# schematic4.net
KiCad netlist of a schematic drawn in Altium Designer
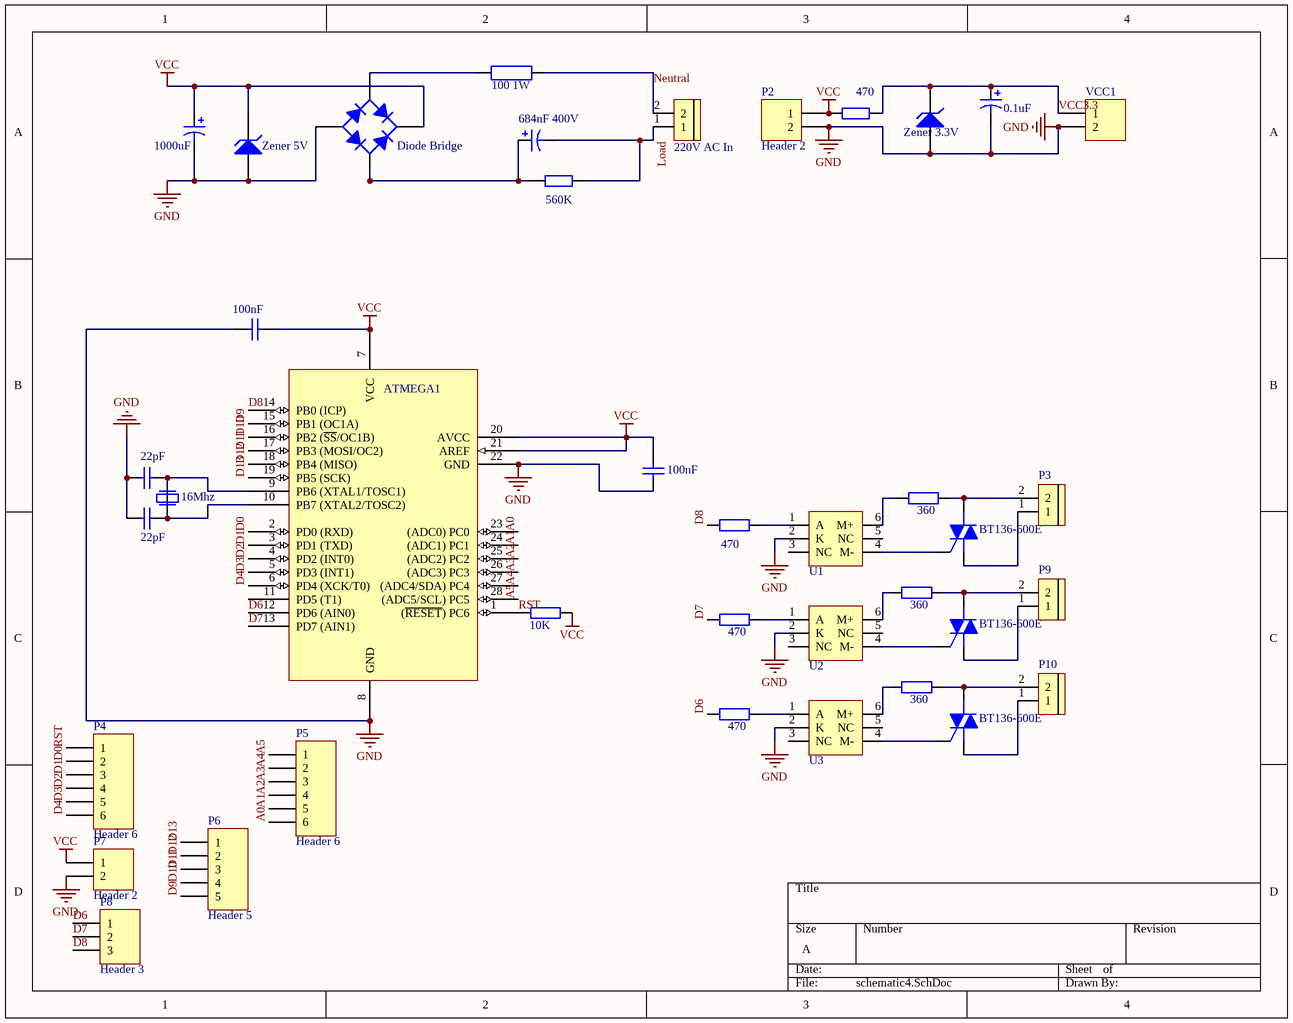
[diagram p0: schematic4.SchDoc]

(export (version "E")
  (design (tool "Eeschema 10.0.6"))
  (components
    (comp (ref "ATMEGA1")
      (value "ATMEGA8_DIP28")
      (footprint "DIP-28")
      (description "Atmel Microcontroller - Library created by carel..  <www.mpfreezone.com>")
      (libsource (lib "AVR") (part "ATMEGA8_DIP28"))
    )
    (comp (ref "C1")
      (value "0.1uF")
      (footprint "C3MM")
      (description "Polarized Capacitor (Axial)")
      (fields (field (name "PUBLISHER") "Altium Limited"))
      (libsource (lib "NBBLib 14-03-2012") (part "Cap Pol 3mm"))
    )
    (comp (ref "C2")
      (value "684nF 400V")
      (footprint "C10mm")
      (description "Polarized Capacitor (Axial)")
      (fields (field (name "PUBLISHER") "Altium Limited"))
      (libsource (lib "NBBLib 14-03-2012") (part "Cap Pol 12mm"))
    )
    (comp (ref "C3")
      (value "1000uF")
      (footprint "C10mm")
      (description "Polarized Capacitor (Axial)")
      (fields (field (name "PUBLISHER") "Altium Limited"))
      (libsource (lib "NBBLib 14-03-2012") (part "Cap Pol 8mm"))
    )
    (comp (ref "C4")
      (value "100nF")
      (footprint "Tu-pico")
      (description "Capacitor")
      (fields (field (name "PUBLISHER") "Altium Limited"))
      (libsource (lib "NBBLib 14-03-2012") (part "CapCeramic"))
    )
    (comp (ref "C5")
      (value "22pF")
      (footprint "Tu-pico")
      (description "Capacitor")
      (fields (field (name "PUBLISHER") "Altium Limited"))
      (libsource (lib "NBBLib 14-03-2012") (part "CapCeramic"))
    )
    (comp (ref "C6")
      (value "100nF")
      (footprint "Tu-pico")
      (description "Capacitor")
      (fields (field (name "PUBLISHER") "Altium Limited"))
      (libsource (lib "NBBLib 14-03-2012") (part "CapCeramic"))
    )
    (comp (ref "C7")
      (value "22pF")
      (footprint "Tu-pico")
      (description "Capacitor")
      (fields (field (name "PUBLISHER") "Altium Limited"))
      (libsource (lib "NBBLib 14-03-2012") (part "CapCeramic"))
    )
    (comp (ref "Crystal1") (value "16Mhz") (footprint "XTAL") (libsource (lib "tung k6") (part "XTAL")))
    (comp (ref "D1")
      (value "Diode Bridge")
      (footprint "D-38")
      (description "Full Wave Diode Bridge")
      (fields (field (name "PUBLISHER") "Altium Limited"))
      (libsource (lib "Miscellaneous Devices") (part "Bridge1"))
    )
    (comp (ref "D2")
      (value "Zener 3.3V")
      (footprint "DIODE/NOM/0.5A")
      (description "Zener Diode")
      (fields (field (name "PUBLISHER") "Altium Limited"))
      (libsource (lib "NBBLib 14-03-2012") (part "Diode Zener"))
    )
    (comp (ref "D3")
      (value "Zener 5V")
      (footprint "DIODE/NOM/0.5A")
      (description "Zener Diode")
      (fields (field (name "VOLTAGE") "5") (field (name "PUBLISHER") "Altium Limited"))
      (libsource (lib "NBBLib 14-03-2012") (part "Diode Zener"))
    )
    (comp (ref "P1")
      (value "220V AC In")
      (footprint "BIG_Header 2")
      (libsource (lib "NBBLib 14-03-2012") (part "BIG_Header 2"))
    )
    (comp (ref "P2")
      (value "Header 2")
      (footprint "HDR1X2")
      (description "Header, 2-Pin")
      (fields (field (name "PUBLISHER") "Altium Limited"))
      (libsource (lib "") (part "Header 2_1"))
    )
    (comp (ref "P3")
      (value "BIG_Header 2")
      (footprint "BIG_Header 2")
      (libsource (lib "NBBLib 14-03-2012") (part "BIG_Header 2"))
    )
    (comp (ref "P4")
      (value "Header 6")
      (footprint "HDR1X6")
      (description "Header, 6-Pin")
      (fields (field (name "PUBLISHER") "Altium Limited"))
      (libsource (lib "Miscellaneous Connectors") (part "Header 6"))
    )
    (comp (ref "P5")
      (value "Header 6")
      (footprint "HDR1X6")
      (description "Header, 6-Pin")
      (fields (field (name "PUBLISHER") "Altium Limited"))
      (libsource (lib "Miscellaneous Connectors") (part "Header 6"))
    )
    (comp (ref "P6")
      (value "Header 5")
      (footprint "HDR1X5")
      (description "Header, 5-Pin")
      (fields (field (name "PUBLISHER") "Altium Limited"))
      (libsource (lib "NBBLib 14-03-2012") (part "Header 5"))
    )
    (comp (ref "P7")
      (value "Header 2")
      (footprint "HDR1X2")
      (description "Header, 2-Pin")
      (fields (field (name "PUBLISHER") "Altium Limited"))
      (libsource (lib "Miscellaneous Connectors") (part "Header 2"))
    )
    (comp (ref "P8")
      (value "Header 3")
      (footprint "HDR1X3")
      (description "Header, 3-Pin")
      (fields (field (name "PUBLISHER") "Altium Limited"))
      (libsource (lib "NBBLib 14-03-2012") (part "Header 3"))
    )
    (comp (ref "P9")
      (value "BIG_Header 2")
      (footprint "BIG_Header 2")
      (libsource (lib "NBBLib 14-03-2012") (part "BIG_Header 2"))
    )
    (comp (ref "P10")
      (value "BIG_Header 2")
      (footprint "BIG_Header 2")
      (libsource (lib "NBBLib 14-03-2012") (part "BIG_Header 2"))
    )
    (comp (ref "Q1")
      (value "BT136-600E")
      (footprint "BTA6-600")
      (description "Silicon Bidirectional Triode Thyristor")
      (fields (field (name "PUBLISHER") "Altium Limited"))
      (libsource (lib "NBBLib 14-03-2012") (part "BTA12-600"))
    )
    (comp (ref "Q2")
      (value "BT136-600E")
      (footprint "BTA6-600")
      (description "Silicon Bidirectional Triode Thyristor")
      (fields (field (name "PUBLISHER") "Altium Limited"))
      (libsource (lib "NBBLib 14-03-2012") (part "BTA12-600"))
    )
    (comp (ref "Q3")
      (value "BT136-600E")
      (footprint "BTA6-600")
      (description "Silicon Bidirectional Triode Thyristor")
      (fields (field (name "PUBLISHER") "Altium Limited"))
      (libsource (lib "NBBLib 14-03-2012") (part "BTA12-600"))
    )
    (comp (ref "R1")
      (value "100 1W")
      (footprint "DIEN TRO 1W (tube)")
      (description "1W Res Power")
      (fields (field (name "VOLTAGE") "400") (field (name "CREATOR") "Nguyen Ba Bien"))
      (libsource (lib "NBBLib 14-03-2012") (part "Res 1W"))
    )
    (comp (ref "R2")
      (value "470")
      (footprint "DIEN TRO 1/4 W")
      (description "Resistor")
      (fields (field (name "Comment") "R0.4W") (field (name "PUBLISHER") "Altium Limited"))
      (libsource (lib "NBBLib 14-03-2012") (part "Res 1/4 W"))
    )
    (comp (ref "R3")
      (value "560K")
      (footprint "AXIAL-0.4")
      (description "Resistor")
      (fields (field (name "PUBLISHER") "Altium Limited"))
      (libsource (lib "Miscellaneous Devices") (part "Res2"))
    )
    (comp (ref "R4")
      (value "470")
      (footprint "R1/4W")
      (description "Resistor")
      (libsource (lib "t.thien") (part "R1/4W"))
    )
    (comp (ref "R5")
      (value "360")
      (footprint "R1/4W")
      (description "Resistor")
      (libsource (lib "t.thien") (part "R1/4W"))
    )
    (comp (ref "R6")
      (value "10K")
      (footprint "R1/4W")
      (description "Resistor")
      (libsource (lib "t.thien") (part "R1/4W"))
    )
    (comp (ref "R7")
      (value "470")
      (footprint "R1/4W")
      (description "Resistor")
      (libsource (lib "t.thien") (part "R1/4W"))
    )
    (comp (ref "R8")
      (value "360")
      (footprint "R1/4W")
      (description "Resistor")
      (libsource (lib "t.thien") (part "R1/4W"))
    )
    (comp (ref "R9")
      (value "470")
      (footprint "R1/4W")
      (description "Resistor")
      (libsource (lib "t.thien") (part "R1/4W"))
    )
    (comp (ref "R10")
      (value "360")
      (footprint "R1/4W")
      (description "Resistor")
      (libsource (lib "t.thien") (part "R1/4W"))
    )
    (comp (ref "U1")
      (value "MOC3021M")
      (footprint "MOC30XX")
      (libsource (lib "NBBLib 14-03-2012") (part "MOC3021M"))
    )
    (comp (ref "U2")
      (value "MOC3021M")
      (footprint "MOC30XX")
      (libsource (lib "NBBLib 14-03-2012") (part "MOC3021M"))
    )
    (comp (ref "U3")
      (value "MOC3021M")
      (footprint "MOC30XX")
      (libsource (lib "NBBLib 14-03-2012") (part "MOC3021M"))
    )
    (comp (ref "VCC1")
      (value "Header 2")
      (footprint "HDR1X2")
      (description "Header, 2-Pin")
      (fields (field (name "PUBLISHER") "Altium Limited"))
      (libsource (lib "NBBLib 14-03-2012") (part "Header 2"))
    )
  )
  (nets
    (net (code "1") (name "/A0") (class "Default")
      (node (ref "ATMEGA1") (pin "23") (pinfunction "(ADC0)_PC0_23") (pintype "bidirectional"))
      (node (ref "P5") (pin "6") (pinfunction "6_6") (pintype "passive"))
    )
    (net (code "2") (name "/A1") (class "Default")
      (node (ref "ATMEGA1") (pin "24") (pinfunction "(ADC1)_PC1_24") (pintype "bidirectional"))
      (node (ref "P5") (pin "5") (pinfunction "5_5") (pintype "passive"))
    )
    (net (code "3") (name "/A2") (class "Default")
      (node (ref "ATMEGA1") (pin "25") (pinfunction "(ADC2)_PC2_25") (pintype "bidirectional"))
      (node (ref "P5") (pin "4") (pinfunction "4_4") (pintype "passive"))
    )
    (net (code "4") (name "/A3") (class "Default")
      (node (ref "ATMEGA1") (pin "26") (pinfunction "(ADC3)_PC3_26") (pintype "bidirectional"))
      (node (ref "P5") (pin "3") (pinfunction "3_3") (pintype "passive"))
    )
    (net (code "5") (name "/A4") (class "Default")
      (node (ref "ATMEGA1") (pin "27") (pinfunction "(ADC4/SDA)_PC4_27") (pintype "bidirectional"))
      (node (ref "P5") (pin "2") (pinfunction "2_2") (pintype "passive"))
    )
    (net (code "6") (name "/A5") (class "Default")
      (node (ref "ATMEGA1") (pin "28") (pinfunction "(ADC5/SCL)_PC5_28") (pintype "bidirectional"))
      (node (ref "P5") (pin "1") (pinfunction "1_1") (pintype "passive"))
    )
    (net (code "7") (name "/D0") (class "Default")
      (node (ref "ATMEGA1") (pin "2") (pinfunction "PD0_(RXD)_2") (pintype "bidirectional"))
      (node (ref "P4") (pin "2") (pinfunction "2_2") (pintype "passive"))
    )
    (net (code "8") (name "/D1") (class "Default")
      (node (ref "ATMEGA1") (pin "3") (pinfunction "PD1_(TXD)_3") (pintype "bidirectional"))
      (node (ref "P4") (pin "3") (pinfunction "3_3") (pintype "passive"))
    )
    (net (code "9") (name "/D2") (class "Default")
      (node (ref "ATMEGA1") (pin "4") (pinfunction "PD2_(INT0)_4") (pintype "bidirectional"))
      (node (ref "P4") (pin "4") (pinfunction "4_4") (pintype "passive"))
    )
    (net (code "10") (name "/D3") (class "Default")
      (node (ref "ATMEGA1") (pin "5") (pinfunction "PD3_(INT1)_5") (pintype "bidirectional"))
      (node (ref "P4") (pin "5") (pinfunction "5_5") (pintype "passive"))
    )
    (net (code "11") (name "/D4") (class "Default")
      (node (ref "ATMEGA1") (pin "6") (pinfunction "PD4_(XCK/T0)_6") (pintype "bidirectional"))
      (node (ref "P4") (pin "6") (pinfunction "6_6") (pintype "passive"))
    )
    (net (code "12") (name "/D6") (class "Default")
      (node (ref "ATMEGA1") (pin "12") (pinfunction "PD6_(AIN0)_12") (pintype "passive"))
      (node (ref "P8") (pin "1") (pinfunction "1_1") (pintype "passive"))
      (node (ref "R9") (pin "1") (pinfunction "1_1") (pintype "passive"))
    )
    (net (code "13") (name "/D7") (class "Default")
      (node (ref "ATMEGA1") (pin "13") (pinfunction "PD7_(AIN1)_13") (pintype "passive"))
      (node (ref "P8") (pin "2") (pinfunction "2_2") (pintype "passive"))
      (node (ref "R7") (pin "1") (pinfunction "1_1") (pintype "passive"))
    )
    (net (code "14") (name "/D8") (class "Default")
      (node (ref "ATMEGA1") (pin "14") (pinfunction "PB0_(ICP)_14") (pintype "bidirectional"))
      (node (ref "P8") (pin "3") (pinfunction "3_3") (pintype "passive"))
      (node (ref "R4") (pin "1") (pinfunction "1_1") (pintype "passive"))
    )
    (net (code "15") (name "/D9") (class "Default")
      (node (ref "ATMEGA1") (pin "15") (pinfunction "PB1_(OC1A)_15") (pintype "bidirectional"))
      (node (ref "P6") (pin "5") (pinfunction "5_5") (pintype "passive"))
    )
    (net (code "16") (name "/D10") (class "Default")
      (node (ref "ATMEGA1") (pin "16") (pinfunction "PB2_(~{SS}/OC1B)_16") (pintype "bidirectional"))
      (node (ref "P6") (pin "4") (pinfunction "4_4") (pintype "passive"))
    )
    (net (code "17") (name "/D11") (class "Default")
      (node (ref "ATMEGA1") (pin "17") (pinfunction "PB3_(MOSI/OC2)_17") (pintype "bidirectional"))
      (node (ref "P6") (pin "3") (pinfunction "3_3") (pintype "passive"))
    )
    (net (code "18") (name "/D12") (class "Default")
      (node (ref "ATMEGA1") (pin "18") (pinfunction "PB4_(MISO)_18") (pintype "bidirectional"))
      (node (ref "P6") (pin "2") (pinfunction "2_2") (pintype "passive"))
    )
    (net (code "19") (name "/D13") (class "Default")
      (node (ref "ATMEGA1") (pin "19") (pinfunction "PB5_(SCK)_19") (pintype "bidirectional"))
      (node (ref "P6") (pin "1") (pinfunction "1_1") (pintype "passive"))
    )
    (net (code "20") (name "/Load") (class "Default")
      (node (ref "C2") (pin "2") (pinfunction "2_2") (pintype "passive"))
      (node (ref "P1") (pin "1") (pinfunction "1_1") (pintype "passive"))
      (node (ref "R3") (pin "2") (pinfunction "2_2") (pintype "passive"))
    )
    (net (code "21") (name "/Neutral") (class "Default")
      (node (ref "P1") (pin "2") (pinfunction "2_2") (pintype "passive"))
      (node (ref "R1") (pin "2") (pinfunction "2_2") (pintype "passive"))
    )
    (net (code "22") (name "/RST") (class "Default")
      (node (ref "ATMEGA1") (pin "1") (pinfunction "(~{RESET})_PC6_1") (pintype "bidirectional"))
      (node (ref "P4") (pin "1") (pinfunction "1_1") (pintype "passive"))
      (node (ref "R6") (pin "2") (pinfunction "2_2") (pintype "passive"))
    )
    (net (code "23") (name "/VCC3.3") (class "Default")
      (node (ref "C1") (pin "1") (pinfunction "1_1") (pintype "passive"))
      (node (ref "D2") (pin "2") (pinfunction "K_2") (pintype "passive"))
      (node (ref "R2") (pin "2") (pinfunction "2_2") (pintype "passive"))
      (node (ref "VCC1") (pin "1") (pinfunction "1_1") (pintype "passive"))
    )
    (net (code "24") (name "GND") (class "Default")
      (node (ref "ATMEGA1") (pin "22") (pinfunction "GND_22") (pintype "passive"))
      (node (ref "ATMEGA1") (pin "8") (pinfunction "GND_8") (pintype "passive"))
      (node (ref "C1") (pin "2") (pinfunction "2_2") (pintype "passive"))
      (node (ref "C3") (pin "2") (pinfunction "2_2") (pintype "passive"))
      (node (ref "C4") (pin "1") (pinfunction "1_1") (pintype "passive"))
      (node (ref "C5") (pin "2") (pinfunction "2_2") (pintype "passive"))
      (node (ref "C6") (pin "1") (pinfunction "1_1") (pintype "passive"))
      (node (ref "C7") (pin "2") (pinfunction "2_2") (pintype "passive"))
      (node (ref "D1") (pin "3") (pinfunction "A_3") (pintype "passive"))
      (node (ref "D2") (pin "1") (pinfunction "A_1") (pintype "passive"))
      (node (ref "D3") (pin "1") (pinfunction "A_1") (pintype "passive"))
      (node (ref "P2") (pin "2") (pinfunction "2_2") (pintype "passive"))
      (node (ref "P7") (pin "2") (pinfunction "2_2") (pintype "passive"))
      (node (ref "U1") (pin "2") (pinfunction "K_2") (pintype "passive"))
      (node (ref "U2") (pin "2") (pinfunction "K_2") (pintype "passive"))
      (node (ref "U3") (pin "2") (pinfunction "K_2") (pintype "passive"))
      (node (ref "VCC1") (pin "2") (pinfunction "2_2") (pintype "passive"))
    )
    (net (code "25") (name "Net-(ATMEGA1-PB6_(XTAL1{slash}TOSC1))") (class "Default")
      (node (ref "ATMEGA1") (pin "10") (pinfunction "PB7_(XTAL2/TOSC2)_10") (pintype "passive"))
      (node (ref "ATMEGA1") (pin "9") (pinfunction "PB6_(XTAL1/TOSC1)_9") (pintype "passive"))
      (node (ref "C5") (pin "1") (pinfunction "1_1") (pintype "passive"))
      (node (ref "C7") (pin "1") (pinfunction "1_1") (pintype "passive"))
      (node (ref "Crystal1") (pin "1") (pinfunction "P1_1") (pintype "passive"))
      (node (ref "Crystal1") (pin "2") (pinfunction "P2_2") (pintype "passive"))
    )
    (net (code "26") (name "Net-(C2-Pad1)") (class "Default")
      (node (ref "C2") (pin "1") (pinfunction "1_1") (pintype "passive"))
      (node (ref "D1") (pin "2") (pinfunction "C_2") (pintype "passive"))
      (node (ref "R3") (pin "1") (pinfunction "1_1") (pintype "passive"))
    )
    (net (code "27") (name "Net-(D1-C-Pad4)") (class "Default")
      (node (ref "D1") (pin "4") (pinfunction "C_4") (pintype "passive"))
      (node (ref "R1") (pin "1") (pinfunction "1_1") (pintype "passive"))
    )
    (net (code "28") (name "Net-(Q1-G)") (class "Default")
      (node (ref "Q1") (pin "3") (pinfunction "G_3") (pintype "passive"))
      (node (ref "U1") (pin "4") (pinfunction "M-_4") (pintype "passive"))
    )
    (net (code "29") (name "Net-(Q1-M1)") (class "Default")
      (node (ref "P3") (pin "1") (pinfunction "1_1") (pintype "passive"))
      (node (ref "Q1") (pin "1") (pinfunction "M1_1") (pintype "passive"))
    )
    (net (code "30") (name "Net-(Q1-M2)") (class "Default")
      (node (ref "P3") (pin "2") (pinfunction "2_2") (pintype "passive"))
      (node (ref "Q1") (pin "2") (pinfunction "M2_2") (pintype "passive"))
      (node (ref "R5") (pin "2") (pinfunction "2_2") (pintype "passive"))
    )
    (net (code "31") (name "Net-(Q2-G)") (class "Default")
      (node (ref "Q2") (pin "3") (pinfunction "G_3") (pintype "passive"))
      (node (ref "U2") (pin "4") (pinfunction "M-_4") (pintype "passive"))
    )
    (net (code "32") (name "Net-(Q2-M1)") (class "Default")
      (node (ref "P9") (pin "1") (pinfunction "1_1") (pintype "passive"))
      (node (ref "Q2") (pin "1") (pinfunction "M1_1") (pintype "passive"))
    )
    (net (code "33") (name "Net-(Q2-M2)") (class "Default")
      (node (ref "P9") (pin "2") (pinfunction "2_2") (pintype "passive"))
      (node (ref "Q2") (pin "2") (pinfunction "M2_2") (pintype "passive"))
      (node (ref "R8") (pin "2") (pinfunction "2_2") (pintype "passive"))
    )
    (net (code "34") (name "Net-(Q3-G)") (class "Default")
      (node (ref "Q3") (pin "3") (pinfunction "G_3") (pintype "passive"))
      (node (ref "U3") (pin "4") (pinfunction "M-_4") (pintype "passive"))
    )
    (net (code "35") (name "Net-(Q3-M1)") (class "Default")
      (node (ref "P10") (pin "1") (pinfunction "1_1") (pintype "passive"))
      (node (ref "Q3") (pin "1") (pinfunction "M1_1") (pintype "passive"))
    )
    (net (code "36") (name "Net-(Q3-M2)") (class "Default")
      (node (ref "P10") (pin "2") (pinfunction "2_2") (pintype "passive"))
      (node (ref "Q3") (pin "2") (pinfunction "M2_2") (pintype "passive"))
      (node (ref "R10") (pin "2") (pinfunction "2_2") (pintype "passive"))
    )
    (net (code "37") (name "Net-(U1-A)") (class "Default")
      (node (ref "R4") (pin "2") (pinfunction "2_2") (pintype "passive"))
      (node (ref "U1") (pin "1") (pinfunction "A_1") (pintype "passive"))
    )
    (net (code "38") (name "Net-(U1-M+)") (class "Default")
      (node (ref "R5") (pin "1") (pinfunction "1_1") (pintype "passive"))
      (node (ref "U1") (pin "6") (pinfunction "M+_6") (pintype "passive"))
    )
    (net (code "39") (name "Net-(U2-A)") (class "Default")
      (node (ref "R7") (pin "2") (pinfunction "2_2") (pintype "passive"))
      (node (ref "U2") (pin "1") (pinfunction "A_1") (pintype "passive"))
    )
    (net (code "40") (name "Net-(U2-M+)") (class "Default")
      (node (ref "R8") (pin "1") (pinfunction "1_1") (pintype "passive"))
      (node (ref "U2") (pin "6") (pinfunction "M+_6") (pintype "passive"))
    )
    (net (code "41") (name "Net-(U3-A)") (class "Default")
      (node (ref "R9") (pin "2") (pinfunction "2_2") (pintype "passive"))
      (node (ref "U3") (pin "1") (pinfunction "A_1") (pintype "passive"))
    )
    (net (code "42") (name "Net-(U3-M+)") (class "Default")
      (node (ref "R10") (pin "1") (pinfunction "1_1") (pintype "passive"))
      (node (ref "U3") (pin "6") (pinfunction "M+_6") (pintype "passive"))
    )
    (net (code "43") (name "VCC") (class "Default")
      (node (ref "ATMEGA1") (pin "20") (pinfunction "AVCC_20") (pintype "passive"))
      (node (ref "ATMEGA1") (pin "21") (pinfunction "AREF_21") (pintype "input"))
      (node (ref "ATMEGA1") (pin "7") (pinfunction "VCC_7") (pintype "passive"))
      (node (ref "C3") (pin "1") (pinfunction "1_1") (pintype "passive"))
      (node (ref "C4") (pin "2") (pinfunction "2_2") (pintype "passive"))
      (node (ref "C6") (pin "2") (pinfunction "2_2") (pintype "passive"))
      (node (ref "D1") (pin "1") (pinfunction "K_1") (pintype "passive"))
      (node (ref "D3") (pin "2") (pinfunction "K_2") (pintype "passive"))
      (node (ref "P2") (pin "1") (pinfunction "1_1") (pintype "passive"))
      (node (ref "P7") (pin "1") (pinfunction "1_1") (pintype "passive"))
      (node (ref "R2") (pin "1") (pinfunction "1_1") (pintype "passive"))
      (node (ref "R6") (pin "1") (pinfunction "1_1") (pintype "passive"))
    )
    (net (code "44") (name "unconnected-(ATMEGA1-PD5_(T1)-Pad11)") (class "Default")
      (node (ref "ATMEGA1") (pin "11") (pinfunction "PD5_(T1)_11") (pintype "passive"))
    )
    (net (code "45") (name "unconnected-(U1-NC-Pad3)") (class "Default")
      (node (ref "U1") (pin "3") (pinfunction "NC_3") (pintype "passive"))
    )
    (net (code "46") (name "unconnected-(U1-NC-Pad5)") (class "Default")
      (node (ref "U1") (pin "5") (pinfunction "NC_5") (pintype "passive"))
    )
    (net (code "47") (name "unconnected-(U2-NC-Pad3)") (class "Default")
      (node (ref "U2") (pin "3") (pinfunction "NC_3") (pintype "passive"))
    )
    (net (code "48") (name "unconnected-(U2-NC-Pad5)") (class "Default")
      (node (ref "U2") (pin "5") (pinfunction "NC_5") (pintype "passive"))
    )
    (net (code "49") (name "unconnected-(U3-NC-Pad3)") (class "Default")
      (node (ref "U3") (pin "3") (pinfunction "NC_3") (pintype "passive"))
    )
    (net (code "50") (name "unconnected-(U3-NC-Pad5)") (class "Default")
      (node (ref "U3") (pin "5") (pinfunction "NC_5") (pintype "passive"))
    )
  )
)
